# TemperatureSense.net
KiCad netlist of a schematic drawn in Altium Designer
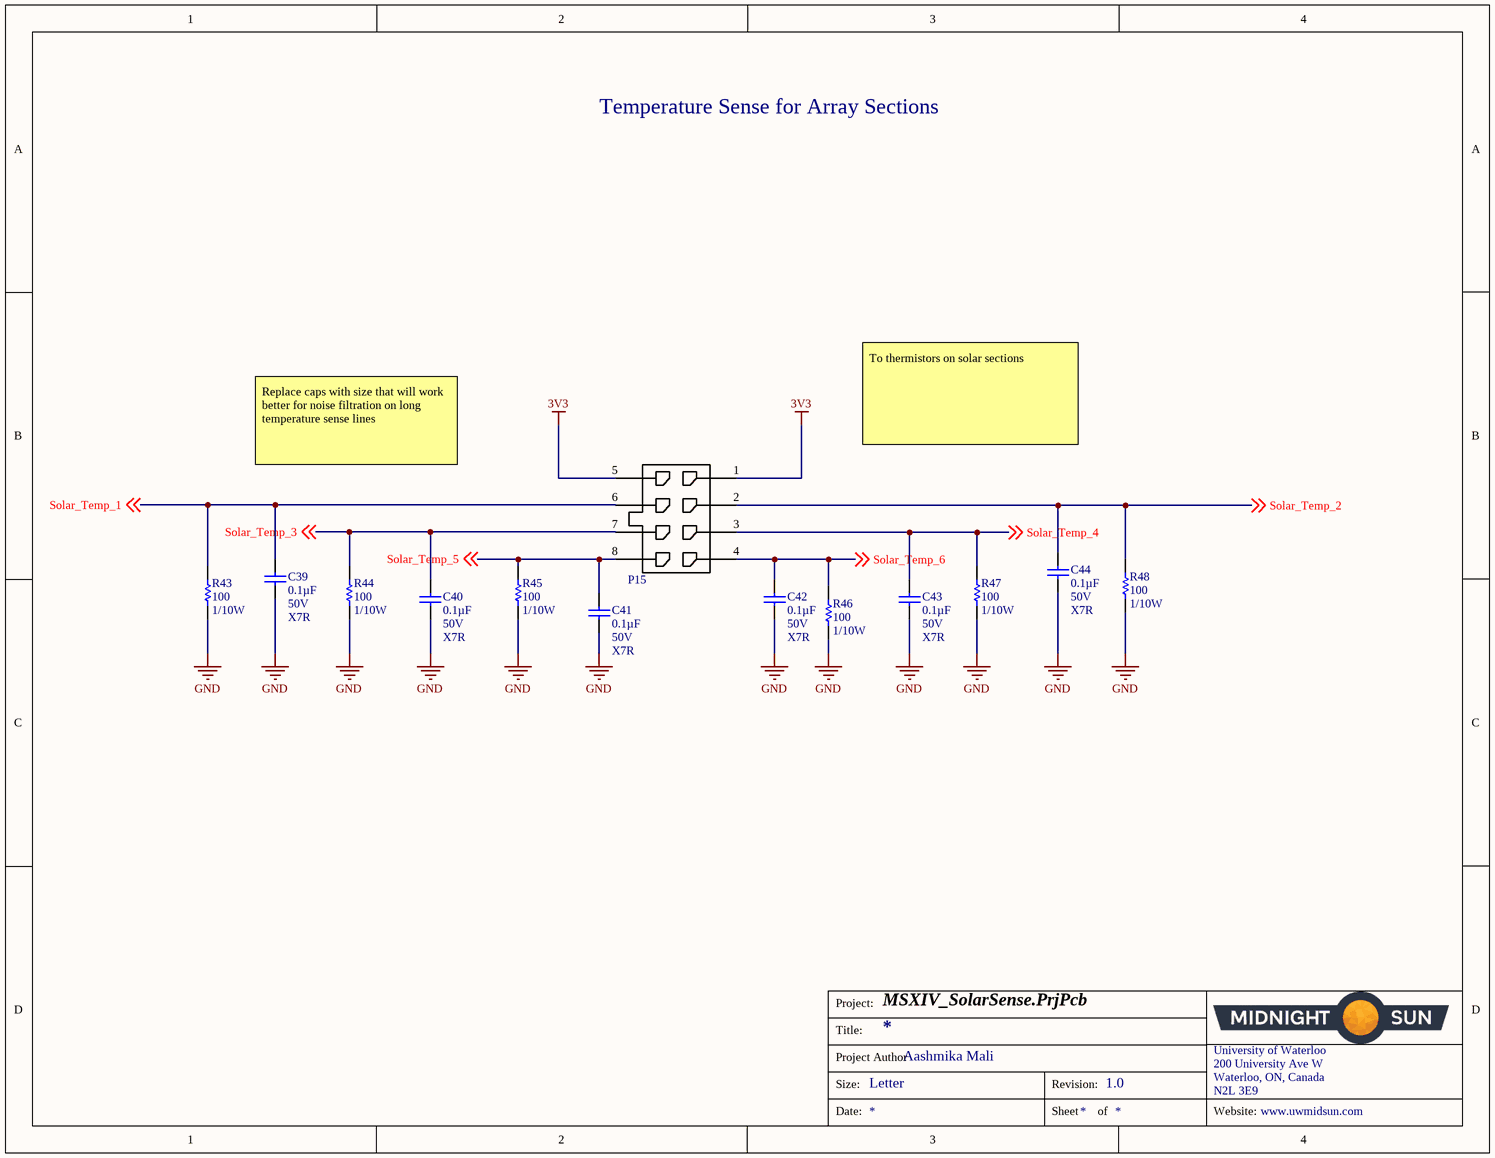
[diagram p0: TemperatureSense.SchDoc]

(export (version "E")
  (design (tool "Eeschema 10.0.6"))
  (components
    (comp (ref "C39")
      (value "CAP CER 0.1UF 50V 10% X7R 0603")
      (footprint "CAP, 0603")
      (description "0.10µF ±10% 50V Ceramic Capacitor X7R 0603 (1608 Metric)")
      (fields
        (field (name "TOLERANCE") "±10%")
        (field (name "CAPACITANCE") "0.1µF")
        (field (name "VOLTAGE") "50V")
        (field (name "TEMPERATURE COEFFICIENT") "X7R")
      )
      (libsource (lib "Schematic Diagrams") (part "CAP CER 0.1UF 50V 10% X7R 0603"))
    )
    (comp (ref "C40")
      (value "CAP CER 0.1UF 50V 10% X7R 0603")
      (footprint "CAP, 0603")
      (description "0.10µF ±10% 50V Ceramic Capacitor X7R 0603 (1608 Metric)")
      (fields
        (field (name "TOLERANCE") "±10%")
        (field (name "CAPACITANCE") "0.1µF")
        (field (name "VOLTAGE") "50V")
        (field (name "TEMPERATURE COEFFICIENT") "X7R")
      )
      (libsource (lib "Schematic Diagrams") (part "CAP CER 0.1UF 50V 10% X7R 0603"))
    )
    (comp (ref "C41")
      (value "CAP CER 0.1UF 50V 10% X7R 0603")
      (footprint "CAP, 0603")
      (description "0.10µF ±10% 50V Ceramic Capacitor X7R 0603 (1608 Metric)")
      (fields
        (field (name "TOLERANCE") "±10%")
        (field (name "CAPACITANCE") "0.1µF")
        (field (name "VOLTAGE") "50V")
        (field (name "TEMPERATURE COEFFICIENT") "X7R")
      )
      (libsource (lib "Schematic Diagrams") (part "CAP CER 0.1UF 50V 10% X7R 0603"))
    )
    (comp (ref "C42")
      (value "CAP CER 0.1UF 50V 10% X7R 0603")
      (footprint "CAP, 0603")
      (description "0.10µF ±10% 50V Ceramic Capacitor X7R 0603 (1608 Metric)")
      (fields
        (field (name "TOLERANCE") "±10%")
        (field (name "CAPACITANCE") "0.1µF")
        (field (name "VOLTAGE") "50V")
        (field (name "TEMPERATURE COEFFICIENT") "X7R")
      )
      (libsource (lib "Schematic Diagrams") (part "CAP CER 0.1UF 50V 10% X7R 0603"))
    )
    (comp (ref "C43")
      (value "CAP CER 0.1UF 50V 10% X7R 0603")
      (footprint "CAP, 0603")
      (description "0.10µF ±10% 50V Ceramic Capacitor X7R 0603 (1608 Metric)")
      (fields
        (field (name "TOLERANCE") "±10%")
        (field (name "CAPACITANCE") "0.1µF")
        (field (name "VOLTAGE") "50V")
        (field (name "TEMPERATURE COEFFICIENT") "X7R")
      )
      (libsource (lib "Schematic Diagrams") (part "CAP CER 0.1UF 50V 10% X7R 0603"))
    )
    (comp (ref "C44")
      (value "CAP CER 0.1UF 50V 10% X7R 0603")
      (footprint "CAP, 0603")
      (description "0.10µF ±10% 50V Ceramic Capacitor X7R 0603 (1608 Metric)")
      (fields
        (field (name "TOLERANCE") "±10%")
        (field (name "CAPACITANCE") "0.1µF")
        (field (name "VOLTAGE") "50V")
        (field (name "TEMPERATURE COEFFICIENT") "X7R")
      )
      (libsource (lib "Schematic Diagrams") (part "CAP CER 0.1UF 50V 10% X7R 0603"))
    )
    (comp (ref "P15")
      (value "CONN 8POS MICRO-FIT 3mm")
      (footprint "CONN, 8POS MICRO-FIT")
      (description "Connector Header Through Hole 6 position 0.118\" (3.00mm)")
      (fields
        (field (name "MANUFACTURER") "Molex, LLC")
        (field (name "MANUFACTURER PART NUMBER") "0430450827")
      )
      (libsource (lib "Schematic Diagrams") (part "CONN 8POS MICRO-FIT 3mm"))
    )
    (comp (ref "R43")
      (value "RES 100 OHM 1% 1/10W 0603")
      (footprint "RES, 0603")
      (description "100 Ohm ±1% 0.1W, 1/10W Chip Resistor 0603 (1608 Metric) Moisture Resistant Thick Film")
      (fields
        (field (name "TOLERANCE") "±1%")
        (field (name "RESISTANCE") "100")
        (field (name "POWER") "1/10W")
      )
      (libsource (lib "Schematic Diagrams") (part "RES 100 OHM 1% 1/10W 0603"))
    )
    (comp (ref "R44")
      (value "RES 100 OHM 1% 1/10W 0603")
      (footprint "RES, 0603")
      (description "100 Ohm ±1% 0.1W, 1/10W Chip Resistor 0603 (1608 Metric) Moisture Resistant Thick Film")
      (fields
        (field (name "TOLERANCE") "±1%")
        (field (name "RESISTANCE") "100")
        (field (name "POWER") "1/10W")
      )
      (libsource (lib "Schematic Diagrams") (part "RES 100 OHM 1% 1/10W 0603"))
    )
    (comp (ref "R45")
      (value "RES 100 OHM 1% 1/10W 0603")
      (footprint "RES, 0603")
      (description "100 Ohm ±1% 0.1W, 1/10W Chip Resistor 0603 (1608 Metric) Moisture Resistant Thick Film")
      (fields
        (field (name "TOLERANCE") "±1%")
        (field (name "RESISTANCE") "100")
        (field (name "POWER") "1/10W")
      )
      (libsource (lib "Schematic Diagrams") (part "RES 100 OHM 1% 1/10W 0603"))
    )
    (comp (ref "R46")
      (value "RES 100 OHM 1% 1/10W 0603")
      (footprint "RES, 0603")
      (description "100 Ohm ±1% 0.1W, 1/10W Chip Resistor 0603 (1608 Metric) Moisture Resistant Thick Film")
      (fields
        (field (name "TOLERANCE") "±1%")
        (field (name "RESISTANCE") "100")
        (field (name "POWER") "1/10W")
      )
      (libsource (lib "Schematic Diagrams") (part "RES 100 OHM 1% 1/10W 0603"))
    )
    (comp (ref "R47")
      (value "RES 100 OHM 1% 1/10W 0603")
      (footprint "RES, 0603")
      (description "100 Ohm ±1% 0.1W, 1/10W Chip Resistor 0603 (1608 Metric) Moisture Resistant Thick Film")
      (fields
        (field (name "TOLERANCE") "±1%")
        (field (name "RESISTANCE") "100")
        (field (name "POWER") "1/10W")
      )
      (libsource (lib "Schematic Diagrams") (part "RES 100 OHM 1% 1/10W 0603"))
    )
    (comp (ref "R48")
      (value "RES 100 OHM 1% 1/10W 0603")
      (footprint "RES, 0603")
      (description "100 Ohm ±1% 0.1W, 1/10W Chip Resistor 0603 (1608 Metric) Moisture Resistant Thick Film")
      (fields
        (field (name "TOLERANCE") "±1%")
        (field (name "RESISTANCE") "100")
        (field (name "POWER") "1/10W")
      )
      (libsource (lib "Schematic Diagrams") (part "RES 100 OHM 1% 1/10W 0603"))
    )
  )
  (nets
    (net (code "1") (name "3V3") (class "Default")
      (node (ref "P15") (pin "1") (pinfunction "1_1") (pintype "passive"))
      (node (ref "P15") (pin "5") (pinfunction "5_5") (pintype "passive"))
    )
    (net (code "2") (name "GND") (class "Default")
      (node (ref "C39") (pin "2") (pinfunction "2_2") (pintype "passive"))
      (node (ref "C40") (pin "2") (pinfunction "2_2") (pintype "passive"))
      (node (ref "C41") (pin "2") (pinfunction "2_2") (pintype "passive"))
      (node (ref "C42") (pin "2") (pinfunction "2_2") (pintype "passive"))
      (node (ref "C43") (pin "2") (pinfunction "2_2") (pintype "passive"))
      (node (ref "C44") (pin "2") (pinfunction "2_2") (pintype "passive"))
      (node (ref "R43") (pin "2") (pinfunction "2_2") (pintype "passive"))
      (node (ref "R44") (pin "2") (pinfunction "2_2") (pintype "passive"))
      (node (ref "R45") (pin "2") (pinfunction "2_2") (pintype "passive"))
      (node (ref "R46") (pin "2") (pinfunction "2_2") (pintype "passive"))
      (node (ref "R47") (pin "2") (pinfunction "2_2") (pintype "passive"))
      (node (ref "R48") (pin "2") (pinfunction "2_2") (pintype "passive"))
    )
    (net (code "3") (name "Solar_Temp_1") (class "Default")
      (node (ref "C39") (pin "1") (pinfunction "1_1") (pintype "passive"))
      (node (ref "P15") (pin "6") (pinfunction "6_6") (pintype "passive"))
      (node (ref "R43") (pin "1") (pinfunction "1_1") (pintype "passive"))
    )
    (net (code "4") (name "Solar_Temp_2") (class "Default")
      (node (ref "C44") (pin "1") (pinfunction "1_1") (pintype "passive"))
      (node (ref "P15") (pin "2") (pinfunction "2_2") (pintype "passive"))
      (node (ref "R48") (pin "1") (pinfunction "1_1") (pintype "passive"))
    )
    (net (code "5") (name "Solar_Temp_3") (class "Default")
      (node (ref "C40") (pin "1") (pinfunction "1_1") (pintype "passive"))
      (node (ref "P15") (pin "7") (pinfunction "7_7") (pintype "passive"))
      (node (ref "R44") (pin "1") (pinfunction "1_1") (pintype "passive"))
    )
    (net (code "6") (name "Solar_Temp_4") (class "Default")
      (node (ref "C43") (pin "1") (pinfunction "1_1") (pintype "passive"))
      (node (ref "P15") (pin "3") (pinfunction "3_3") (pintype "passive"))
      (node (ref "R47") (pin "1") (pinfunction "1_1") (pintype "passive"))
    )
    (net (code "7") (name "Solar_Temp_5") (class "Default")
      (node (ref "C41") (pin "1") (pinfunction "1_1") (pintype "passive"))
      (node (ref "P15") (pin "8") (pinfunction "8_8") (pintype "passive"))
      (node (ref "R45") (pin "1") (pinfunction "1_1") (pintype "passive"))
    )
    (net (code "8") (name "Solar_Temp_6") (class "Default")
      (node (ref "C42") (pin "1") (pinfunction "1_1") (pintype "passive"))
      (node (ref "P15") (pin "4") (pinfunction "4_4") (pintype "passive"))
      (node (ref "R46") (pin "1") (pinfunction "1_1") (pintype "passive"))
    )
  )
)
